# LM2587_BoostConverter.net
KiCad netlist of a schematic drawn in Altium Designer
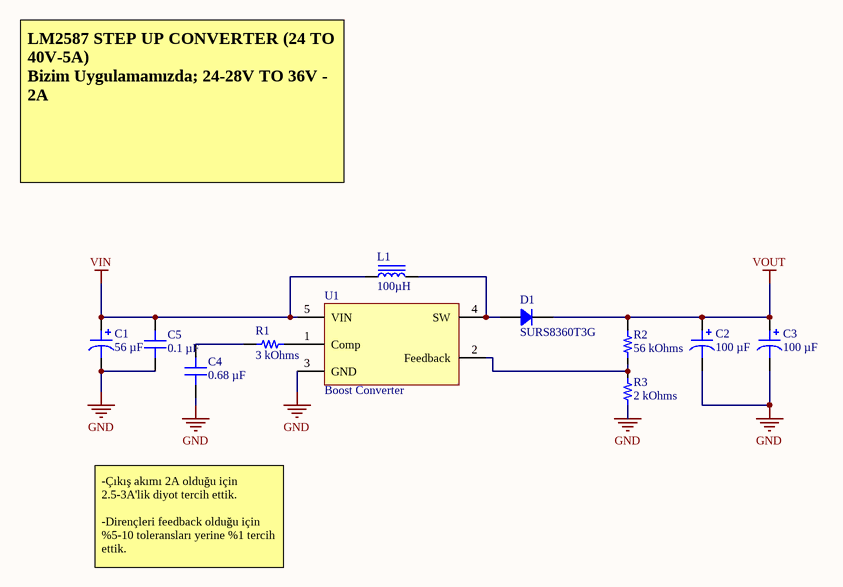
[diagram p0: LM2587_BoostConverter.SchDoc]

(export (version "E")
  (design (tool "Eeschema 10.0.6"))
  (components
    (comp (ref "C1")
      (value "56 µF")
      (footprint "CAP ALSMD 6.6MM H7.7MM")
      (description "CAP ALUM 56UF 20% 35V SMD")
      (fields (field (name "PART NUMBER") "UUD1V560MCL1GS") (field (name "MANUFACTURER") "Nichicon"))
      (libsource (lib "Celestial Altium Library - altium_library") (part "Polarised Capacitor"))
    )
    (comp (ref "C2")
      (value "100 µF")
      (footprint "CAP ALSMD 8.3MM H10.5MM")
      (description "CAP ALUM 100UF 20% 50V SMD")
      (fields (field (name "PART NUMBER") "UWT1H101MNL1GS") (field (name "MANUFACTURER") "Nichicon"))
      (libsource (lib "Celestial Altium Library - altium_library") (part "Polarised Capacitor"))
    )
    (comp (ref "C3")
      (value "100 µF")
      (footprint "CAP ALSMD 8.3MM H10.5MM")
      (description "CAP ALUM 100UF 20% 50V SMD")
      (fields (field (name "PART NUMBER") "UWT1H101MNL1GS") (field (name "MANUFACTURER") "Nichicon"))
      (libsource (lib "Celestial Altium Library - altium_library") (part "Polarised Capacitor"))
    )
    (comp (ref "C4")
      (value "0.68 µF")
      (footprint "CAP 0805_2012")
      (description "CAP CER 0.68UF 50V X7R 0805")
      (fields
        (field (name "PART NUMBER") "CGA4J3X7R1H684K125AB")
        (field (name "MANUFACTURER") "TDK Corporation")
      )
      (libsource (lib "Celestial Altium Library - altium_library") (part "Capacitor"))
    )
    (comp (ref "C5")
      (value "0.1 µF")
      (footprint "CAP 0805_2012")
      (description "CAP CER 0.1UF 50V X7R 0805")
      (fields (field (name "PART NUMBER") "CC0805MRX7R9BB104") (field (name "MANUFACTURER") "Yageo"))
      (libsource (lib "Celestial Altium Library - altium_library") (part "Capacitor"))
    )
    (comp (ref "D1")
      (value "SURS8360T3G")
      (footprint "DO214AB SMC")
      (description "DIODE GEN PURP 600V 3A SMC")
      (fields (field (name "MANUFACTURER") "ON Semiconductor"))
      (libsource (lib "Celestial Altium Library - altium_library") (part "Diode"))
    )
    (comp (ref "L1")
      (value "100µH")
      (footprint "7447070")
      (description "FIXED IND 100UH 170MA 5.85 OHM")
      (fields (field (name "PART NUMBER") "CB2016T101KV") (field (name "MANUFACTURER") "Taiyo Yuden"))
      (libsource (lib "Celestial Altium Library - altium_library") (part "Inductor"))
    )
    (comp (ref "R1")
      (value "3 kOhms")
      (footprint "RES 0805_2012")
      (description "RES SMD 3K OHM 1% 1/8W 0805")
      (fields
        (field (name "PART NUMBER") "ERJ-6ENF3001V")
        (field (name "MANUFACTURER") "Panasonic Electronic Components")
      )
      (libsource (lib "Celestial Altium Library - altium_library") (part "Resistor"))
    )
    (comp (ref "R2")
      (value "56 kOhms")
      (footprint "RES 0805_2012")
      (description "RES 56K OHM 1% 1/3W 0805")
      (fields
        (field (name "PART NUMBER") "CRGP0805F56K")
        (field (name "MANUFACTURER") "TE Connectivity Passive Product")
      )
      (libsource (lib "Celestial Altium Library - altium_library") (part "Resistor"))
    )
    (comp (ref "R3")
      (value "2 kOhms")
      (footprint "RES 0805_2012")
      (description "RES SMD 2K OHM 1% 0.4W 0805")
      (fields (field (name "PART NUMBER") "RCS08052K00FKEA") (field (name "MANUFACTURER") "Vishay Dale"))
      (libsource (lib "Celestial Altium Library - altium_library") (part "Resistor"))
    )
    (comp (ref "U1")
      (value "Boost Converter")
      (footprint "AltiumLive:D2PAK")
      (libsource (lib "AltiumLive") (part "LM2587"))
    )
  )
  (nets
    (net (code "1") (name "GND") (class "Default")
      (node (ref "C1") (pin "2") (pinfunction "2_2") (pintype "passive"))
      (node (ref "C2") (pin "2") (pinfunction "2_2") (pintype "passive"))
      (node (ref "C3") (pin "2") (pinfunction "2_2") (pintype "passive"))
      (node (ref "C4") (pin "1") (pinfunction "1_1") (pintype "passive"))
      (node (ref "C5") (pin "1") (pinfunction "1_1") (pintype "passive"))
      (node (ref "R3") (pin "1") (pinfunction "1_1") (pintype "passive"))
      (node (ref "U1") (pin "3") (pinfunction "GND_3") (pintype "passive"))
    )
    (net (code "2") (name "Net-(C4-Pad2)") (class "Default")
      (node (ref "C4") (pin "2") (pinfunction "2_2") (pintype "passive"))
      (node (ref "R1") (pin "1") (pinfunction "1_1") (pintype "passive"))
    )
    (net (code "3") (name "Net-(U1-Comp)") (class "Default")
      (node (ref "R1") (pin "2") (pinfunction "2_2") (pintype "passive"))
      (node (ref "U1") (pin "1") (pinfunction "Comp_1") (pintype "passive"))
    )
    (net (code "4") (name "Net-(U1-Feedback)") (class "Default")
      (node (ref "R2") (pin "1") (pinfunction "1_1") (pintype "passive"))
      (node (ref "R3") (pin "2") (pinfunction "2_2") (pintype "passive"))
      (node (ref "U1") (pin "2") (pinfunction "Feedback_2") (pintype "passive"))
    )
    (net (code "5") (name "Net-(U1-SW)") (class "Default")
      (node (ref "D1") (pin "1") (pinfunction "1_1") (pintype "passive"))
      (node (ref "L1") (pin "2") (pinfunction "2_2") (pintype "passive"))
      (node (ref "U1") (pin "4") (pinfunction "SW_4") (pintype "passive"))
    )
    (net (code "6") (name "VIN") (class "Default")
      (node (ref "C1") (pin "1") (pinfunction "1_1") (pintype "passive"))
      (node (ref "C5") (pin "2") (pinfunction "2_2") (pintype "passive"))
      (node (ref "L1") (pin "1") (pinfunction "1_1") (pintype "passive"))
      (node (ref "U1") (pin "5") (pinfunction "VIN_5") (pintype "passive"))
    )
    (net (code "7") (name "VOUT") (class "Default")
      (node (ref "C2") (pin "1") (pinfunction "1_1") (pintype "passive"))
      (node (ref "C3") (pin "1") (pinfunction "1_1") (pintype "passive"))
      (node (ref "D1") (pin "2") (pinfunction "2_2") (pintype "passive"))
      (node (ref "R2") (pin "2") (pinfunction "2_2") (pintype "passive"))
    )
  )
)
